# pico32_remote_v1_0.net
KiCad netlist of a schematic drawn in EAGLE
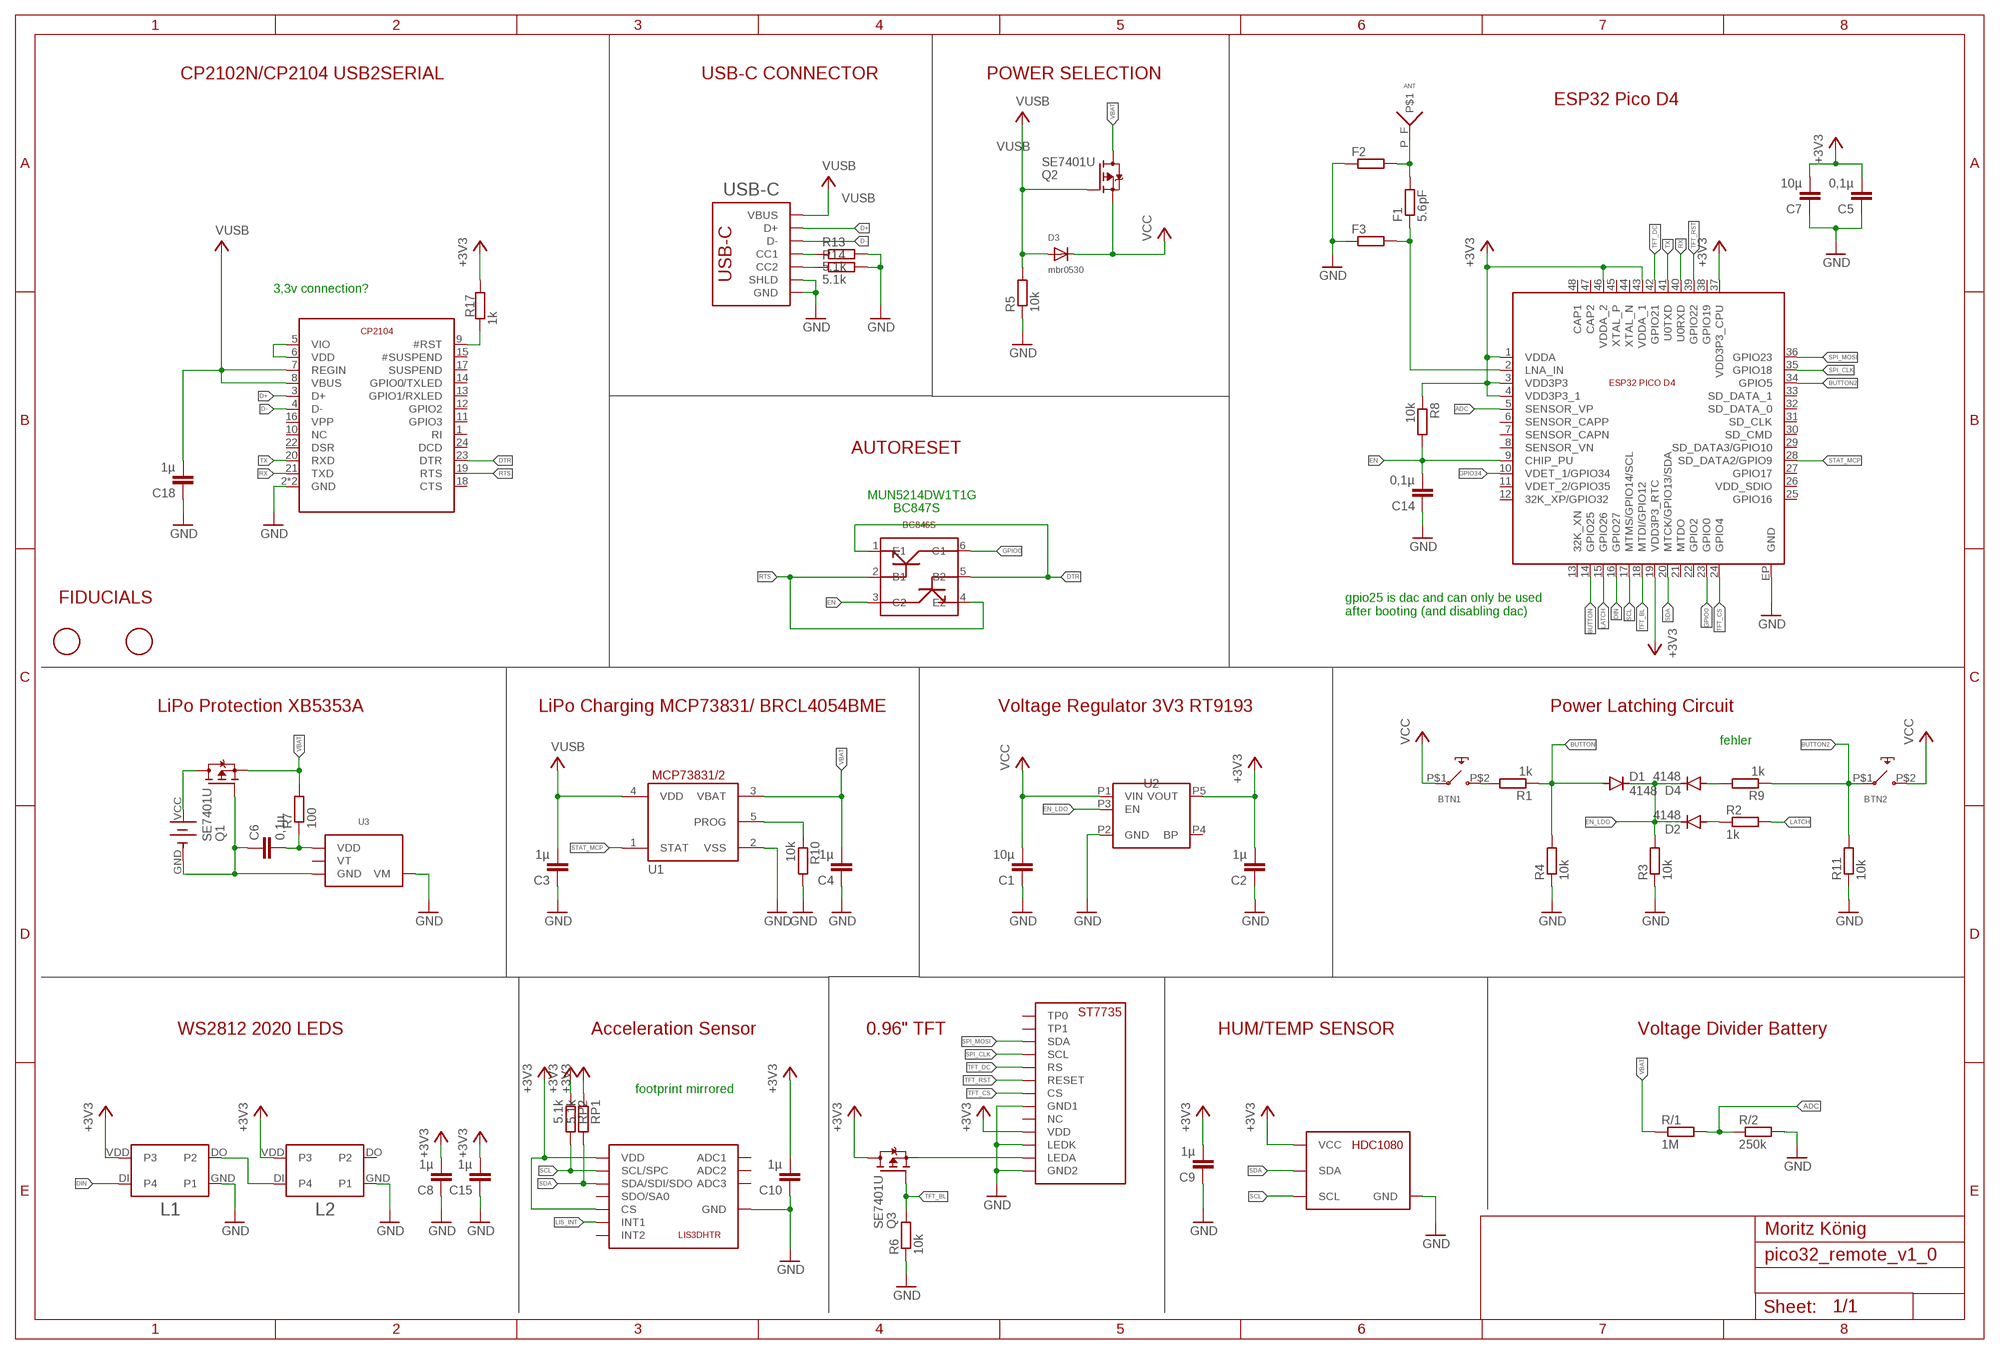
[diagram p0: schematic, sheet 1]

(export (version "E")
  (design (tool "Eeschema 10.0.6"))
  (components
    (comp (ref "ANT")
      (value "MOLEX_ANT_3D")
      (footprint "eagle-import:MOLEX_ANT_3D")
      (libsource (lib "eagle-import") (part "MOLEX_ANT_3D"))
    )
    (comp (ref "BTN1")
      (value "BUTTON_6X6_SILICON")
      (footprint "eagle-import:BUTTON_SILICON")
      (libsource (lib "eagle-import") (part "BUTTON_6X6_SILICON"))
    )
    (comp (ref "BTN2")
      (value "BUTTON_6X6_SILICON")
      (footprint "eagle-import:BUTTON_SILICON")
      (libsource (lib "eagle-import") (part "BUTTON_6X6_SILICON"))
    )
    (comp (ref "C1")
      (value "10µ")
      (footprint "eagle-import:C0603")
      (libsource (lib "eagle-import") (part "C-EU_WO_KEEPOUT"))
    )
    (comp (ref "C2")
      (value "1µ")
      (footprint "eagle-import:C0603")
      (libsource (lib "eagle-import") (part "C-EU_WO_KEEPOUT"))
    )
    (comp (ref "C3")
      (value "1µ")
      (footprint "eagle-import:R0402")
      (libsource (lib "eagle-import") (part "C-EU-0402-WOKEEPOUT_R"))
    )
    (comp (ref "C4")
      (value "1µ")
      (footprint "eagle-import:R0402")
      (libsource (lib "eagle-import") (part "C-EU-0402-WOKEEPOUT_R"))
    )
    (comp (ref "C5")
      (value "0,1µ")
      (footprint "eagle-import:C0603")
      (libsource (lib "eagle-import") (part "C-EU_WO_KEEPOUT"))
    )
    (comp (ref "C6")
      (value "0,1µ")
      (footprint "eagle-import:R0402")
      (libsource (lib "eagle-import") (part "C-EU-0402-WOKEEPOUT_R"))
    )
    (comp (ref "C7")
      (value "10µ")
      (footprint "eagle-import:C0603")
      (libsource (lib "eagle-import") (part "C-EU_WO_KEEPOUT"))
    )
    (comp (ref "C8")
      (value "1µ")
      (footprint "eagle-import:R0402")
      (libsource (lib "eagle-import") (part "C-EU-0402-WOKEEPOUT_R"))
    )
    (comp (ref "C9")
      (value "1µ")
      (footprint "eagle-import:R0402")
      (libsource (lib "eagle-import") (part "C-EU-0402-WOKEEPOUT_R"))
    )
    (comp (ref "C10")
      (value "1µ")
      (footprint "eagle-import:R0402")
      (libsource (lib "eagle-import") (part "C-EU-0402-WOKEEPOUT_R"))
    )
    (comp (ref "C14")
      (value "0,1µ")
      (footprint "eagle-import:C0402K")
      (libsource (lib "eagle-import") (part "C-EUC0402K"))
    )
    (comp (ref "C15")
      (value "1µ")
      (footprint "eagle-import:R0402")
      (libsource (lib "eagle-import") (part "C-EU-0402-WOKEEPOUT_R"))
    )
    (comp (ref "C18")
      (value "1µ")
      (footprint "eagle-import:R0402")
      (libsource (lib "eagle-import") (part "C-EU-0402-WOKEEPOUT_R"))
    )
    (comp (ref "D1")
      (value "4148")
      (footprint "eagle-import:SOD523")
      (libsource (lib "eagle-import") (part "DIODE-SOD523"))
    )
    (comp (ref "D2")
      (value "4148")
      (footprint "eagle-import:SOD523")
      (libsource (lib "eagle-import") (part "DIODE-SOD523"))
    )
    (comp (ref "D3")
      (value "mbr0530")
      (footprint "eagle-import:SOD-123FL")
      (libsource (lib "eagle-import") (part "DIODE_SOD-123FL"))
    )
    (comp (ref "D4")
      (value "4148")
      (footprint "eagle-import:SOD523")
      (libsource (lib "eagle-import") (part "DIODE-SOD523"))
    )
    (comp (ref "ESP32")
      (value "ESP32_PICO_D4_LP")
      (footprint "eagle-import:QFN-48_LONG")
      (libsource (lib "eagle-import") (part "ESP32_PICO_D4_LP"))
    )
    (comp (ref "F1")
      (value "5.6pF")
      (footprint "eagle-import:R0402")
      (libsource (lib "eagle-import") (part "R-EU-0402-WOKEEPOUT"))
    )
    (comp (ref "F2")
      (value "R-EU-0402-WOKEEPOUT")
      (footprint "eagle-import:R0402")
      (libsource (lib "eagle-import") (part "R-EU-0402-WOKEEPOUT"))
    )
    (comp (ref "F3")
      (value "R-EU-0402-WOKEEPOUT")
      (footprint "eagle-import:R0402")
      (libsource (lib "eagle-import") (part "R-EU-0402-WOKEEPOUT"))
    )
    (comp (ref "L1")
      (value "WS2812_2020")
      (footprint "eagle-import:WS2812_2020")
      (libsource (lib "eagle-import") (part "WS2812_2020"))
    )
    (comp (ref "L2")
      (value "WS2812_2020")
      (footprint "eagle-import:WS2812_2020")
      (libsource (lib "eagle-import") (part "WS2812_2020"))
    )
    (comp (ref "Q1")
      (value "SE7401U")
      (footprint "eagle-import:SOT323")
      (libsource (lib "eagle-import") (part "SE7401U"))
    )
    (comp (ref "Q2")
      (value "SE7401U")
      (footprint "eagle-import:SOT323")
      (libsource (lib "eagle-import") (part "SE7401U"))
    )
    (comp (ref "Q3")
      (value "SE7401U")
      (footprint "eagle-import:SOT323")
      (libsource (lib "eagle-import") (part "SE7401U"))
    )
    (comp (ref "R/1")
      (value "1M")
      (footprint "eagle-import:R0402")
      (libsource (lib "eagle-import") (part "R-EU-0402-WOKEEPOUT"))
    )
    (comp (ref "R/2")
      (value "250k")
      (footprint "eagle-import:R0402")
      (libsource (lib "eagle-import") (part "R-EU-0402-WOKEEPOUT"))
    )
    (comp (ref "R1")
      (value "1k")
      (footprint "eagle-import:R0402")
      (libsource (lib "eagle-import") (part "R-EU-0402-WOKEEPOUT"))
    )
    (comp (ref "R2")
      (value "1k")
      (footprint "eagle-import:R0402")
      (libsource (lib "eagle-import") (part "R-EU-0402-WOKEEPOUT"))
    )
    (comp (ref "R3")
      (value "10k")
      (footprint "eagle-import:R0402")
      (libsource (lib "eagle-import") (part "R-EU-0402-WOKEEPOUT"))
    )
    (comp (ref "R4")
      (value "10k")
      (footprint "eagle-import:R0402")
      (libsource (lib "eagle-import") (part "R-EU-0402-WOKEEPOUT"))
    )
    (comp (ref "R5")
      (value "10k")
      (footprint "eagle-import:R0402")
      (libsource (lib "eagle-import") (part "R-EU-0402-WOKEEPOUT"))
    )
    (comp (ref "R6")
      (value "10k")
      (footprint "eagle-import:R0402")
      (libsource (lib "eagle-import") (part "R-EU-0402-WOKEEPOUT"))
    )
    (comp (ref "R7")
      (value "100")
      (footprint "eagle-import:R0402")
      (libsource (lib "eagle-import") (part "R-EU-0402-WOKEEPOUT"))
    )
    (comp (ref "R8")
      (value "10k")
      (footprint "eagle-import:R0402")
      (libsource (lib "eagle-import") (part "R-EU-0402-WOKEEPOUT"))
    )
    (comp (ref "R9")
      (value "1k")
      (footprint "eagle-import:R0402")
      (libsource (lib "eagle-import") (part "R-EU-0402-WOKEEPOUT"))
    )
    (comp (ref "R10")
      (value "10k")
      (footprint "eagle-import:R0402")
      (libsource (lib "eagle-import") (part "R-EU-0402-WOKEEPOUT"))
    )
    (comp (ref "R11")
      (value "10k")
      (footprint "eagle-import:R0402")
      (libsource (lib "eagle-import") (part "R-EU-0402-WOKEEPOUT"))
    )
    (comp (ref "R13")
      (value "5.1k")
      (footprint "eagle-import:R0402")
      (libsource (lib "eagle-import") (part "R-EU-0402-WOKEEPOUT"))
    )
    (comp (ref "R14")
      (value "5.1k")
      (footprint "eagle-import:R0402")
      (libsource (lib "eagle-import") (part "R-EU-0402-WOKEEPOUT"))
    )
    (comp (ref "R17")
      (value "1k")
      (footprint "eagle-import:R0402")
      (libsource (lib "eagle-import") (part "R-EU-0402-WOKEEPOUT"))
    )
    (comp (ref "RP1")
      (value "5.1k")
      (footprint "eagle-import:R0402")
      (libsource (lib "eagle-import") (part "R-EU-0402-WOKEEPOUT"))
    )
    (comp (ref "RP2")
      (value "5.1k")
      (footprint "eagle-import:R0402")
      (libsource (lib "eagle-import") (part "R-EU-0402-WOKEEPOUT"))
    )
    (comp (ref "U$2")
      (value "2450_BATTERYHOLDER_SMD")
      (footprint "eagle-import:2450_BATTERYHOLDER_SMD")
      (libsource (lib "eagle-import") (part "2450_BATTERYHOLDER_SMD"))
    )
    (comp (ref "U$4")
      (value "ST7735_096TFT_TWISTED")
      (footprint "eagle-import:ST7735_096TFT_TWISTED")
      (libsource (lib "eagle-import") (part "ST7735_096TFT_TWISTED"))
    )
    (comp (ref "U$6")
      (value "FIDUCIAL")
      (footprint "eagle-import:FIDUCIAL_1MM")
      (libsource (lib "eagle-import") (part "FIDUCIAL"))
    )
    (comp (ref "U$7")
      (value "FIDUCIAL")
      (footprint "eagle-import:FIDUCIAL_1MM")
      (libsource (lib "eagle-import") (part "FIDUCIAL"))
    )
    (comp (ref "U1")
      (value "BRCL4054BME")
      (footprint "eagle-import:SOT23-5L")
      (libsource (lib "eagle-import") (part "MCP73831/OT"))
    )
    (comp (ref "U2")
      (value "RT9193_SC70-5")
      (footprint "eagle-import:SC-70-5")
      (libsource (lib "eagle-import") (part "RT9193_SC70-5"))
    )
    (comp (ref "U3")
      (value "XB5353A")
      (footprint "eagle-import:SOT23-5")
      (libsource (lib "eagle-import") (part "XB5353A"))
    )
    (comp (ref "U4")
      (value "LIS3DHTR")
      (footprint "eagle-import:LGA_16_LIS3DHTR")
      (libsource (lib "eagle-import") (part "LIS3DHTR"))
    )
    (comp (ref "U5")
      (value "CP2102N")
      (footprint "eagle-import:QFN24-4X4")
      (libsource (lib "eagle-import") (part "CP2104"))
    )
    (comp (ref "U6")
      (value "MUN5214DW1T1G")
      (footprint "eagle-import:SOT363")
      (libsource (lib "eagle-import") (part "BC846S"))
    )
    (comp (ref "U7")
      (value "HDC1080")
      (footprint "eagle-import:WSON08_HDC1080")
      (libsource (lib "eagle-import") (part "HDC1080"))
    )
    (comp (ref "USB-C")
      (value "USB_C_C393939")
      (footprint "eagle-import:USBC_C393939")
      (libsource (lib "eagle-import") (part "USB_C_C393939"))
    )
  )
  (nets
    (net (code "1") (name "+3V3") (class "Default")
      (node (ref "C10") (pin "2") (pinfunction "2_2") (pintype "passive"))
      (node (ref "C15") (pin "2") (pinfunction "2_2") (pintype "passive"))
      (node (ref "C2") (pin "2") (pinfunction "2_2") (pintype "passive"))
      (node (ref "C5") (pin "2") (pinfunction "2_2") (pintype "passive"))
      (node (ref "C7") (pin "2") (pinfunction "2_2") (pintype "passive"))
      (node (ref "C8") (pin "2") (pinfunction "2_2") (pintype "passive"))
      (node (ref "C9") (pin "2") (pinfunction "2_2") (pintype "passive"))
      (node (ref "ESP32") (pin "1") (pinfunction "VDDA_1") (pintype "bidirectional"))
      (node (ref "ESP32") (pin "19") (pinfunction "VDD3P3_RTC_19") (pintype "bidirectional"))
      (node (ref "ESP32") (pin "3") (pinfunction "VDD3P3_3") (pintype "bidirectional"))
      (node (ref "ESP32") (pin "37") (pinfunction "VDD3P3_CPU_37") (pintype "bidirectional"))
      (node (ref "ESP32") (pin "4") (pinfunction "VDD3P3_1_4") (pintype "bidirectional"))
      (node (ref "ESP32") (pin "43") (pinfunction "VDDA_1_43") (pintype "bidirectional"))
      (node (ref "ESP32") (pin "46") (pinfunction "VDDA_2_46") (pintype "bidirectional"))
      (node (ref "L1") (pin "VDD") (pinfunction "P3_VDD") (pintype "bidirectional"))
      (node (ref "L2") (pin "VDD") (pinfunction "P3_VDD") (pintype "bidirectional"))
      (node (ref "Q3") (pin "3") (pinfunction "D_3") (pintype "passive"))
      (node (ref "R17") (pin "2") (pinfunction "2_2") (pintype "passive"))
      (node (ref "R8") (pin "1") (pinfunction "1_1") (pintype "passive"))
      (node (ref "RP1") (pin "1") (pinfunction "1_1") (pintype "passive"))
      (node (ref "RP2") (pin "1") (pinfunction "1_1") (pintype "passive"))
      (node (ref "U$4") (pin "P10") (pinfunction "VDD_P10") (pintype "bidirectional"))
      (node (ref "U2") (pin "P5") (pinfunction "VOUT_P5") (pintype "bidirectional"))
      (node (ref "U4") (pin "P$1") (pinfunction "VDD_P$1") (pintype "bidirectional"))
      (node (ref "U4") (pin "P$14") (pinfunction "VDD_P$14") (pintype "bidirectional"))
      (node (ref "U4") (pin "P$8") (pinfunction "CS_P$8") (pintype "bidirectional"))
      (node (ref "U7") (pin "P5") (pinfunction "VCC_P5") (pintype "bidirectional"))
    )
    (net (code "2") (name "ADC") (class "Default")
      (node (ref "ESP32") (pin "5") (pinfunction "SENSOR_VP_5") (pintype "bidirectional"))
      (node (ref "R/1") (pin "2") (pinfunction "2_2") (pintype "passive"))
      (node (ref "R/2") (pin "1") (pinfunction "1_1") (pintype "passive"))
    )
    (net (code "3") (name "BUTTON") (class "Default")
      (node (ref "D1") (pin "A") (pinfunction "A_A") (pintype "passive"))
      (node (ref "ESP32") (pin "14") (pinfunction "GPIO25_14") (pintype "bidirectional"))
      (node (ref "R1") (pin "1") (pinfunction "1_1") (pintype "passive"))
      (node (ref "R4") (pin "2") (pinfunction "2_2") (pintype "passive"))
    )
    (net (code "4") (name "BUTTON2") (class "Default")
      (node (ref "BTN2") (pin "P$1") (pinfunction "P1_P$1") (pintype "bidirectional"))
      (node (ref "ESP32") (pin "34") (pinfunction "GPIO5_34") (pintype "bidirectional"))
      (node (ref "R11") (pin "2") (pinfunction "2_2") (pintype "passive"))
      (node (ref "R9") (pin "1") (pinfunction "1_1") (pintype "passive"))
    )
    (net (code "5") (name "D+") (class "Default")
      (node (ref "U5") (pin "3") (pinfunction "D+_3") (pintype "bidirectional"))
      (node (ref "USB-C") (pin "A6") (pinfunction "D+_A6") (pintype "bidirectional"))
      (node (ref "USB-C") (pin "B6") (pinfunction "D+_B6") (pintype "bidirectional"))
    )
    (net (code "6") (name "D-") (class "Default")
      (node (ref "U5") (pin "4") (pinfunction "D-_4") (pintype "bidirectional"))
      (node (ref "USB-C") (pin "A7") (pinfunction "D-_A7") (pintype "bidirectional"))
      (node (ref "USB-C") (pin "B7") (pinfunction "D-_B7") (pintype "bidirectional"))
    )
    (net (code "7") (name "DIN") (class "Default")
      (node (ref "ESP32") (pin "16") (pinfunction "GPIO27_16") (pintype "bidirectional"))
      (node (ref "L1") (pin "DI") (pinfunction "P4_DI") (pintype "bidirectional"))
    )
    (net (code "8") (name "DTR") (class "Default")
      (node (ref "U5") (pin "23") (pinfunction "DTR_23") (pintype "bidirectional"))
      (node (ref "U6") (pin "1") (pinfunction "E1_1") (pintype "bidirectional"))
      (node (ref "U6") (pin "5") (pinfunction "B2_5") (pintype "bidirectional"))
    )
    (net (code "9") (name "EN") (class "Default")
      (node (ref "C14") (pin "2") (pinfunction "2_2") (pintype "passive"))
      (node (ref "ESP32") (pin "9") (pinfunction "CHIP_PU_9") (pintype "bidirectional"))
      (node (ref "R8") (pin "2") (pinfunction "2_2") (pintype "passive"))
      (node (ref "U6") (pin "3") (pinfunction "C2_3") (pintype "bidirectional"))
    )
    (net (code "10") (name "EN_LDO") (class "Default")
      (node (ref "D1") (pin "C") (pinfunction "C_C") (pintype "passive"))
      (node (ref "D2") (pin "C") (pinfunction "C_C") (pintype "passive"))
      (node (ref "D4") (pin "C") (pinfunction "C_C") (pintype "passive"))
      (node (ref "R3") (pin "2") (pinfunction "2_2") (pintype "passive"))
      (node (ref "U2") (pin "P3") (pinfunction "EN_P3") (pintype "bidirectional"))
    )
    (net (code "11") (name "GND") (class "Default")
      (node (ref "C1") (pin "1") (pinfunction "1_1") (pintype "passive"))
      (node (ref "C10") (pin "1") (pinfunction "1_1") (pintype "passive"))
      (node (ref "C14") (pin "1") (pinfunction "1_1") (pintype "passive"))
      (node (ref "C15") (pin "1") (pinfunction "1_1") (pintype "passive"))
      (node (ref "C18") (pin "1") (pinfunction "1_1") (pintype "passive"))
      (node (ref "C2") (pin "1") (pinfunction "1_1") (pintype "passive"))
      (node (ref "C3") (pin "1") (pinfunction "1_1") (pintype "passive"))
      (node (ref "C4") (pin "1") (pinfunction "1_1") (pintype "passive"))
      (node (ref "C5") (pin "1") (pinfunction "1_1") (pintype "passive"))
      (node (ref "C7") (pin "1") (pinfunction "1_1") (pintype "passive"))
      (node (ref "C8") (pin "1") (pinfunction "1_1") (pintype "passive"))
      (node (ref "C9") (pin "1") (pinfunction "1_1") (pintype "passive"))
      (node (ref "ESP32") (pin "EP") (pinfunction "GND_EP") (pintype "bidirectional"))
      (node (ref "F2") (pin "1") (pinfunction "1_1") (pintype "passive"))
      (node (ref "F3") (pin "1") (pinfunction "1_1") (pintype "passive"))
      (node (ref "L1") (pin "GND") (pinfunction "P1_GND") (pintype "bidirectional"))
      (node (ref "L2") (pin "GND") (pinfunction "P1_GND") (pintype "bidirectional"))
      (node (ref "R/2") (pin "2") (pinfunction "2_2") (pintype "passive"))
      (node (ref "R10") (pin "2") (pinfunction "2_2") (pintype "passive"))
      (node (ref "R11") (pin "1") (pinfunction "1_1") (pintype "passive"))
      (node (ref "R13") (pin "2") (pinfunction "2_2") (pintype "passive"))
      (node (ref "R14") (pin "2") (pinfunction "2_2") (pintype "passive"))
      (node (ref "R3") (pin "1") (pinfunction "1_1") (pintype "passive"))
      (node (ref "R4") (pin "1") (pinfunction "1_1") (pintype "passive"))
      (node (ref "R5") (pin "1") (pinfunction "1_1") (pintype "passive"))
      (node (ref "R6") (pin "1") (pinfunction "1_1") (pintype "passive"))
      (node (ref "U$4") (pin "P11") (pinfunction "LEDK_P11") (pintype "bidirectional"))
      (node (ref "U$4") (pin "P13") (pinfunction "GND2_P13") (pintype "bidirectional"))
      (node (ref "U$4") (pin "P8") (pinfunction "GND1_P8") (pintype "bidirectional"))
      (node (ref "U1") (pin "2") (pinfunction "VSS_2") (pintype "power_in"))
      (node (ref "U2") (pin "P2") (pinfunction "GND_P2") (pintype "bidirectional"))
      (node (ref "U3") (pin "4") (pinfunction "VM_4") (pintype "bidirectional"))
      (node (ref "U3") (pin "5") (pinfunction "VM_5") (pintype "bidirectional"))
      (node (ref "U4") (pin "P$10") (pinfunction "GND_P$10") (pintype "bidirectional"))
      (node (ref "U4") (pin "P$12") (pinfunction "GND_P$12") (pintype "bidirectional"))
      (node (ref "U4") (pin "P$5") (pinfunction "GND_P$5") (pintype "bidirectional"))
      (node (ref "U5") (pin "2") (pinfunction "GND_2") (pintype "bidirectional"))
      (node (ref "U5") (pin "EXP") (pinfunction "GND_EXP") (pintype "bidirectional"))
      (node (ref "U7") (pin "P2") (pinfunction "GND_P2") (pintype "bidirectional"))
      (node (ref "USB-C") (pin "A1B12") (pinfunction "GND_A1B12") (pintype "bidirectional"))
      (node (ref "USB-C") (pin "B1A12") (pinfunction "GND_B1A12") (pintype "bidirectional"))
      (node (ref "USB-C") (pin "S1") (pinfunction "SHLD_S1") (pintype "bidirectional"))
      (node (ref "USB-C") (pin "S2") (pinfunction "SHLD_S2") (pintype "bidirectional"))
      (node (ref "USB-C") (pin "S3") (pinfunction "SHLD_S3") (pintype "bidirectional"))
      (node (ref "USB-C") (pin "S4") (pinfunction "SHLD_S4") (pintype "bidirectional"))
    )
    (net (code "12") (name "GPIO0") (class "Default")
      (node (ref "ESP32") (pin "23") (pinfunction "GPIO0_23") (pintype "bidirectional"))
      (node (ref "U6") (pin "6") (pinfunction "C1_6") (pintype "bidirectional"))
    )
    (net (code "13") (name "GPIO34") (class "Default")
      (node (ref "ESP32") (pin "10") (pinfunction "VDET_1/GPIO34_10") (pintype "bidirectional"))
    )
    (net (code "14") (name "LATCH") (class "Default")
      (node (ref "ESP32") (pin "15") (pinfunction "GPIO26_15") (pintype "bidirectional"))
      (node (ref "R2") (pin "2") (pinfunction "2_2") (pintype "passive"))
    )
    (net (code "15") (name "LIS_INT") (class "Default")
      (node (ref "U4") (pin "P$11") (pinfunction "INT1_P$11") (pintype "bidirectional"))
    )
    (net (code "16") (name "Net-(ANT-P$1)") (class "Default")
      (node (ref "ANT") (pin "P_F") (pinfunction "P$1_P_F") (pintype "bidirectional"))
      (node (ref "F1") (pin "2") (pinfunction "2_2") (pintype "passive"))
      (node (ref "F2") (pin "2") (pinfunction "2_2") (pintype "passive"))
    )
    (net (code "17") (name "Net-(BTN1-P2)") (class "Default")
      (node (ref "BTN1") (pin "P$2") (pinfunction "P2_P$2") (pintype "bidirectional"))
      (node (ref "R1") (pin "2") (pinfunction "2_2") (pintype "passive"))
    )
    (net (code "18") (name "Net-(D2-PadA)") (class "Default")
      (node (ref "D2") (pin "A") (pinfunction "A_A") (pintype "passive"))
      (node (ref "R2") (pin "1") (pinfunction "1_1") (pintype "passive"))
    )
    (net (code "19") (name "Net-(D4-PadA)") (class "Default")
      (node (ref "D4") (pin "A") (pinfunction "A_A") (pintype "passive"))
      (node (ref "R9") (pin "2") (pinfunction "2_2") (pintype "passive"))
    )
    (net (code "20") (name "Net-(ESP32-LNA_IN)") (class "Default")
      (node (ref "ESP32") (pin "2") (pinfunction "LNA_IN_2") (pintype "bidirectional"))
      (node (ref "F1") (pin "1") (pinfunction "1_1") (pintype "passive"))
      (node (ref "F3") (pin "2") (pinfunction "2_2") (pintype "passive"))
    )
    (net (code "21") (name "Net-(L1-P2)") (class "Default")
      (node (ref "L1") (pin "DO") (pinfunction "P2_DO") (pintype "bidirectional"))
      (node (ref "L2") (pin "DI") (pinfunction "P4_DI") (pintype "bidirectional"))
    )
    (net (code "22") (name "Net-(Q1-D)") (class "Default")
      (node (ref "Q1") (pin "3") (pinfunction "D_3") (pintype "passive"))
      (node (ref "U$2") (pin "VCC") (pinfunction "VCC_VCC") (pintype "bidirectional"))
    )
    (net (code "23") (name "Net-(Q1-G)") (class "Default")
      (node (ref "C6") (pin "1") (pinfunction "1_1") (pintype "passive"))
      (node (ref "Q1") (pin "1") (pinfunction "G_1") (pintype "passive"))
      (node (ref "U$2") (pin "GND") (pinfunction "GND_GND") (pintype "bidirectional"))
      (node (ref "U3") (pin "2") (pinfunction "GND_2") (pintype "bidirectional"))
    )
    (net (code "24") (name "Net-(Q3-S)") (class "Default")
      (node (ref "Q3") (pin "2") (pinfunction "S_2") (pintype "passive"))
      (node (ref "U$4") (pin "P12") (pinfunction "LEDA_P12") (pintype "bidirectional"))
    )
    (net (code "25") (name "Net-(U1-PROG)") (class "Default")
      (node (ref "R10") (pin "1") (pinfunction "1_1") (pintype "passive"))
      (node (ref "U1") (pin "5") (pinfunction "PROG_5") (pintype "input"))
    )
    (net (code "26") (name "Net-(U3-VDD)") (class "Default")
      (node (ref "C6") (pin "2") (pinfunction "2_2") (pintype "passive"))
      (node (ref "R7") (pin "1") (pinfunction "1_1") (pintype "passive"))
      (node (ref "U3") (pin "3") (pinfunction "VDD_3") (pintype "bidirectional"))
    )
    (net (code "27") (name "Net-(U5-#RST)") (class "Default")
      (node (ref "R17") (pin "1") (pinfunction "1_1") (pintype "passive"))
      (node (ref "U5") (pin "9") (pinfunction "#RST_9") (pintype "bidirectional"))
    )
    (net (code "28") (name "Net-(U5-VDD)") (class "Default")
      (node (ref "U5") (pin "5") (pinfunction "VIO_5") (pintype "bidirectional"))
      (node (ref "U5") (pin "6") (pinfunction "VDD_6") (pintype "bidirectional"))
    )
    (net (code "29") (name "Net-(USB-C-CC1)") (class "Default")
      (node (ref "R13") (pin "1") (pinfunction "1_1") (pintype "passive"))
      (node (ref "USB-C") (pin "A5") (pinfunction "CC1_A5") (pintype "bidirectional"))
    )
    (net (code "30") (name "Net-(USB-C-CC2)") (class "Default")
      (node (ref "R14") (pin "1") (pinfunction "1_1") (pintype "passive"))
      (node (ref "USB-C") (pin "B5") (pinfunction "CC2_B5") (pintype "bidirectional"))
    )
    (net (code "31") (name "RTS") (class "Default")
      (node (ref "U5") (pin "19") (pinfunction "RTS_19") (pintype "bidirectional"))
      (node (ref "U6") (pin "2") (pinfunction "B1_2") (pintype "bidirectional"))
      (node (ref "U6") (pin "4") (pinfunction "E2_4") (pintype "bidirectional"))
    )
    (net (code "32") (name "RX") (class "Default")
      (node (ref "ESP32") (pin "40") (pinfunction "U0RXD_40") (pintype "bidirectional"))
      (node (ref "U5") (pin "21") (pinfunction "TXD_21") (pintype "bidirectional"))
    )
    (net (code "33") (name "SCL") (class "Default")
      (node (ref "ESP32") (pin "17") (pinfunction "MTMS/GPIO14/SCL_17") (pintype "bidirectional"))
      (node (ref "RP2") (pin "2") (pinfunction "2_2") (pintype "passive"))
      (node (ref "U4") (pin "P$4") (pinfunction "SCL/SPC_P$4") (pintype "bidirectional"))
      (node (ref "U7") (pin "P6") (pinfunction "SCL_P6") (pintype "bidirectional"))
    )
    (net (code "34") (name "SDA") (class "Default")
      (node (ref "ESP32") (pin "20") (pinfunction "MTCK/GPIO13/SDA_20") (pintype "bidirectional"))
      (node (ref "RP1") (pin "2") (pinfunction "2_2") (pintype "passive"))
      (node (ref "U4") (pin "P$6") (pinfunction "SDA/SDI/SDO_P$6") (pintype "bidirectional"))
      (node (ref "U7") (pin "P1") (pinfunction "SDA_P1") (pintype "bidirectional"))
    )
    (net (code "35") (name "SPI_CLK") (class "Default")
      (node (ref "ESP32") (pin "35") (pinfunction "GPIO18_35") (pintype "bidirectional"))
      (node (ref "U$4") (pin "P4") (pinfunction "SCL_P4") (pintype "bidirectional"))
    )
    (net (code "36") (name "SPI_MOSI") (class "Default")
      (node (ref "ESP32") (pin "36") (pinfunction "GPIO23_36") (pintype "bidirectional"))
      (node (ref "U$4") (pin "P3") (pinfunction "SDA_P3") (pintype "bidirectional"))
    )
    (net (code "37") (name "STAT_MCP") (class "Default")
      (node (ref "ESP32") (pin "28") (pinfunction "SD_DATA2/GPIO9_28") (pintype "bidirectional"))
      (node (ref "U1") (pin "1") (pinfunction "STAT_1") (pintype "output"))
    )
    (net (code "38") (name "TFT_BL") (class "Default")
      (node (ref "ESP32") (pin "18") (pinfunction "MTDI/GPIO12_18") (pintype "bidirectional"))
      (node (ref "Q3") (pin "1") (pinfunction "G_1") (pintype "passive"))
      (node (ref "R6") (pin "2") (pinfunction "2_2") (pintype "passive"))
    )
    (net (code "39") (name "TFT_CS") (class "Default")
      (node (ref "ESP32") (pin "24") (pinfunction "GPIO4_24") (pintype "bidirectional"))
      (node (ref "U$4") (pin "P7") (pinfunction "CS_P7") (pintype "bidirectional"))
    )
    (net (code "40") (name "TFT_DC") (class "Default")
      (node (ref "ESP32") (pin "42") (pinfunction "GPIO21_42") (pintype "bidirectional"))
      (node (ref "U$4") (pin "P5") (pinfunction "RS_P5") (pintype "bidirectional"))
    )
    (net (code "41") (name "TFT_RST") (class "Default")
      (node (ref "ESP32") (pin "39") (pinfunction "GPIO22_39") (pintype "bidirectional"))
      (node (ref "U$4") (pin "P6") (pinfunction "RESET_P6") (pintype "bidirectional"))
    )
    (net (code "42") (name "TX") (class "Default")
      (node (ref "ESP32") (pin "41") (pinfunction "U0TXD_41") (pintype "bidirectional"))
      (node (ref "U5") (pin "20") (pinfunction "RXD_20") (pintype "bidirectional"))
    )
    (net (code "43") (name "VBAT") (class "Default")
      (node (ref "C4") (pin "2") (pinfunction "2_2") (pintype "passive"))
      (node (ref "Q1") (pin "2") (pinfunction "S_2") (pintype "passive"))
      (node (ref "Q2") (pin "3") (pinfunction "D_3") (pintype "passive"))
      (node (ref "R/1") (pin "1") (pinfunction "1_1") (pintype "passive"))
      (node (ref "R7") (pin "2") (pinfunction "2_2") (pintype "passive"))
      (node (ref "U1") (pin "3") (pinfunction "VBAT_3") (pintype "bidirectional"))
    )
    (net (code "44") (name "VCC") (class "Default")
      (node (ref "BTN1") (pin "P$1") (pinfunction "P1_P$1") (pintype "bidirectional"))
      (node (ref "BTN2") (pin "P$2") (pinfunction "P2_P$2") (pintype "bidirectional"))
      (node (ref "C1") (pin "2") (pinfunction "2_2") (pintype "passive"))
      (node (ref "D3") (pin "C") (pinfunction "C_C") (pintype "passive"))
      (node (ref "Q2") (pin "2") (pinfunction "S_2") (pintype "passive"))
      (node (ref "U2") (pin "P1") (pinfunction "VIN_P1") (pintype "bidirectional"))
    )
    (net (code "45") (name "VUSB") (class "Default")
      (node (ref "C18") (pin "2") (pinfunction "2_2") (pintype "passive"))
      (node (ref "C3") (pin "2") (pinfunction "2_2") (pintype "passive"))
      (node (ref "D3") (pin "A") (pinfunction "A_A") (pintype "passive"))
      (node (ref "Q2") (pin "1") (pinfunction "G_1") (pintype "passive"))
      (node (ref "R5") (pin "2") (pinfunction "2_2") (pintype "passive"))
      (node (ref "U1") (pin "4") (pinfunction "VDD_4") (pintype "power_in"))
      (node (ref "U5") (pin "7") (pinfunction "REGIN_7") (pintype "bidirectional"))
      (node (ref "U5") (pin "8") (pinfunction "VBUS_8") (pintype "bidirectional"))
      (node (ref "USB-C") (pin "A4B9") (pinfunction "VBUS_A4B9") (pintype "bidirectional"))
      (node (ref "USB-C") (pin "B4A9") (pinfunction "VBUS_B4A9") (pintype "bidirectional"))
    )
    (net (code "46") (name "unconnected-(ESP32-32K_XN-Pad13)") (class "Default")
      (node (ref "ESP32") (pin "13") (pinfunction "32K_XN_13") (pintype "bidirectional"))
    )
    (net (code "47") (name "unconnected-(ESP32-32K_XP{slash}GPIO32-Pad12)") (class "Default")
      (node (ref "ESP32") (pin "12") (pinfunction "32K_XP/GPIO32_12") (pintype "bidirectional"))
    )
    (net (code "48") (name "unconnected-(ESP32-CAP1-Pad48)") (class "Default")
      (node (ref "ESP32") (pin "48") (pinfunction "CAP1_48") (pintype "bidirectional"))
    )
    (net (code "49") (name "unconnected-(ESP32-CAP2-Pad47)") (class "Default")
      (node (ref "ESP32") (pin "47") (pinfunction "CAP2_47") (pintype "bidirectional"))
    )
    (net (code "50") (name "unconnected-(ESP32-GPIO2-Pad22)") (class "Default")
      (node (ref "ESP32") (pin "22") (pinfunction "GPIO2_22") (pintype "bidirectional"))
    )
    (net (code "51") (name "unconnected-(ESP32-GPIO16-Pad25)") (class "Default")
      (node (ref "ESP32") (pin "25") (pinfunction "GPIO16_25") (pintype "bidirectional"))
    )
    (net (code "52") (name "unconnected-(ESP32-GPIO17-Pad27)") (class "Default")
      (node (ref "ESP32") (pin "27") (pinfunction "GPIO17_27") (pintype "bidirectional"))
    )
    (net (code "53") (name "unconnected-(ESP32-GPIO19-Pad38)") (class "Default")
      (node (ref "ESP32") (pin "38") (pinfunction "GPIO19_38") (pintype "bidirectional"))
    )
    (net (code "54") (name "unconnected-(ESP32-MTDO-Pad21)") (class "Default")
      (node (ref "ESP32") (pin "21") (pinfunction "MTDO_21") (pintype "bidirectional"))
    )
    (net (code "55") (name "unconnected-(ESP32-SD_CLK-Pad31)") (class "Default")
      (node (ref "ESP32") (pin "31") (pinfunction "SD_CLK_31") (pintype "bidirectional"))
    )
    (net (code "56") (name "unconnected-(ESP32-SD_CMD-Pad30)") (class "Default")
      (node (ref "ESP32") (pin "30") (pinfunction "SD_CMD_30") (pintype "bidirectional"))
    )
    (net (code "57") (name "unconnected-(ESP32-SD_DATA3{slash}GPIO10-Pad29)") (class "Default")
      (node (ref "ESP32") (pin "29") (pinfunction "SD_DATA3/GPIO10_29") (pintype "bidirectional"))
    )
    (net (code "58") (name "unconnected-(ESP32-SD_DATA_0-Pad32)") (class "Default")
      (node (ref "ESP32") (pin "32") (pinfunction "SD_DATA_0_32") (pintype "bidirectional"))
    )
    (net (code "59") (name "unconnected-(ESP32-SD_DATA_1-Pad33)") (class "Default")
      (node (ref "ESP32") (pin "33") (pinfunction "SD_DATA_1_33") (pintype "bidirectional"))
    )
    (net (code "60") (name "unconnected-(ESP32-SENSOR_CAPN-Pad7)") (class "Default")
      (node (ref "ESP32") (pin "7") (pinfunction "SENSOR_CAPN_7") (pintype "bidirectional"))
    )
    (net (code "61") (name "unconnected-(ESP32-SENSOR_CAPP-Pad6)") (class "Default")
      (node (ref "ESP32") (pin "6") (pinfunction "SENSOR_CAPP_6") (pintype "bidirectional"))
    )
    (net (code "62") (name "unconnected-(ESP32-SENSOR_VN-Pad8)") (class "Default")
      (node (ref "ESP32") (pin "8") (pinfunction "SENSOR_VN_8") (pintype "bidirectional"))
    )
    (net (code "63") (name "unconnected-(ESP32-VDD_SDIO-Pad26)") (class "Default")
      (node (ref "ESP32") (pin "26") (pinfunction "VDD_SDIO_26") (pintype "bidirectional"))
    )
    (net (code "64") (name "unconnected-(ESP32-VDET_2{slash}GPIO35-Pad11)") (class "Default")
      (node (ref "ESP32") (pin "11") (pinfunction "VDET_2/GPIO35_11") (pintype "bidirectional"))
    )
    (net (code "65") (name "unconnected-(ESP32-XTAL_N-Pad44)") (class "Default")
      (node (ref "ESP32") (pin "44") (pinfunction "XTAL_N_44") (pintype "bidirectional"))
    )
    (net (code "66") (name "unconnected-(ESP32-XTAL_P-Pad45)") (class "Default")
      (node (ref "ESP32") (pin "45") (pinfunction "XTAL_P_45") (pintype "bidirectional"))
    )
    (net (code "67") (name "unconnected-(L2-P2-PadDO)") (class "Default")
      (node (ref "L2") (pin "DO") (pinfunction "P2_DO") (pintype "bidirectional"))
    )
    (net (code "68") (name "unconnected-(U$4-NC-PadP9)") (class "Default")
      (node (ref "U$4") (pin "P9") (pinfunction "NC_P9") (pintype "bidirectional"))
    )
    (net (code "69") (name "unconnected-(U$4-TP0-PadP1)") (class "Default")
      (node (ref "U$4") (pin "P1") (pinfunction "TP0_P1") (pintype "bidirectional"))
    )
    (net (code "70") (name "unconnected-(U$4-TP1-PadP2)") (class "Default")
      (node (ref "U$4") (pin "P2") (pinfunction "TP1_P2") (pintype "bidirectional"))
    )
    (net (code "71") (name "unconnected-(U2-BP-PadP4)") (class "Default")
      (node (ref "U2") (pin "P4") (pinfunction "BP_P4") (pintype "bidirectional"))
    )
    (net (code "72") (name "unconnected-(U3-VT-Pad1)") (class "Default")
      (node (ref "U3") (pin "1") (pinfunction "VT_1") (pintype "bidirectional"))
    )
    (net (code "73") (name "unconnected-(U4-ADC1-PadP$16)") (class "Default")
      (node (ref "U4") (pin "P$16") (pinfunction "ADC1_P$16") (pintype "bidirectional"))
    )
    (net (code "74") (name "unconnected-(U4-ADC2-PadP$15)") (class "Default")
      (node (ref "U4") (pin "P$15") (pinfunction "ADC2_P$15") (pintype "bidirectional"))
    )
    (net (code "75") (name "unconnected-(U4-ADC3-PadP$13)") (class "Default")
      (node (ref "U4") (pin "P$13") (pinfunction "ADC3_P$13") (pintype "bidirectional"))
    )
    (net (code "76") (name "unconnected-(U4-INT2-PadP$9)") (class "Default")
      (node (ref "U4") (pin "P$9") (pinfunction "INT2_P$9") (pintype "bidirectional"))
    )
    (net (code "77") (name "unconnected-(U4-SDO{slash}SA0-PadP$7)") (class "Default")
      (node (ref "U4") (pin "P$7") (pinfunction "SDO/SA0_P$7") (pintype "bidirectional"))
    )
    (net (code "78") (name "unconnected-(U5-#SUSPEND-Pad15)") (class "Default")
      (node (ref "U5") (pin "15") (pinfunction "#SUSPEND_15") (pintype "bidirectional"))
    )
    (net (code "79") (name "unconnected-(U5-CTS-Pad18)") (class "Default")
      (node (ref "U5") (pin "18") (pinfunction "CTS_18") (pintype "bidirectional"))
    )
    (net (code "80") (name "unconnected-(U5-DCD-Pad24)") (class "Default")
      (node (ref "U5") (pin "24") (pinfunction "DCD_24") (pintype "bidirectional"))
    )
    (net (code "81") (name "unconnected-(U5-DSR-Pad22)") (class "Default")
      (node (ref "U5") (pin "22") (pinfunction "DSR_22") (pintype "bidirectional"))
    )
    (net (code "82") (name "unconnected-(U5-GPIO0{slash}TXLED-Pad14)") (class "Default")
      (node (ref "U5") (pin "14") (pinfunction "GPIO0/TXLED_14") (pintype "bidirectional"))
    )
    (net (code "83") (name "unconnected-(U5-GPIO1{slash}RXLED-Pad13)") (class "Default")
      (node (ref "U5") (pin "13") (pinfunction "GPIO1/RXLED_13") (pintype "bidirectional"))
    )
    (net (code "84") (name "unconnected-(U5-GPIO2-Pad12)") (class "Default")
      (node (ref "U5") (pin "12") (pinfunction "GPIO2_12") (pintype "bidirectional"))
    )
    (net (code "85") (name "unconnected-(U5-GPIO3-Pad11)") (class "Default")
      (node (ref "U5") (pin "11") (pinfunction "GPIO3_11") (pintype "bidirectional"))
    )
    (net (code "86") (name "unconnected-(U5-NC-Pad10)") (class "Default")
      (node (ref "U5") (pin "10") (pinfunction "NC_10") (pintype "bidirectional"))
    )
    (net (code "87") (name "unconnected-(U5-RI-Pad1)") (class "Default")
      (node (ref "U5") (pin "1") (pinfunction "RI_1") (pintype "bidirectional"))
    )
    (net (code "88") (name "unconnected-(U5-SUSPEND-Pad17)") (class "Default")
      (node (ref "U5") (pin "17") (pinfunction "SUSPEND_17") (pintype "bidirectional"))
    )
    (net (code "89") (name "unconnected-(U5-VPP-Pad16)") (class "Default")
      (node (ref "U5") (pin "16") (pinfunction "VPP_16") (pintype "bidirectional"))
    )
  )
)
